# LCD.net
KiCad netlist of a schematic drawn in Altium Designer
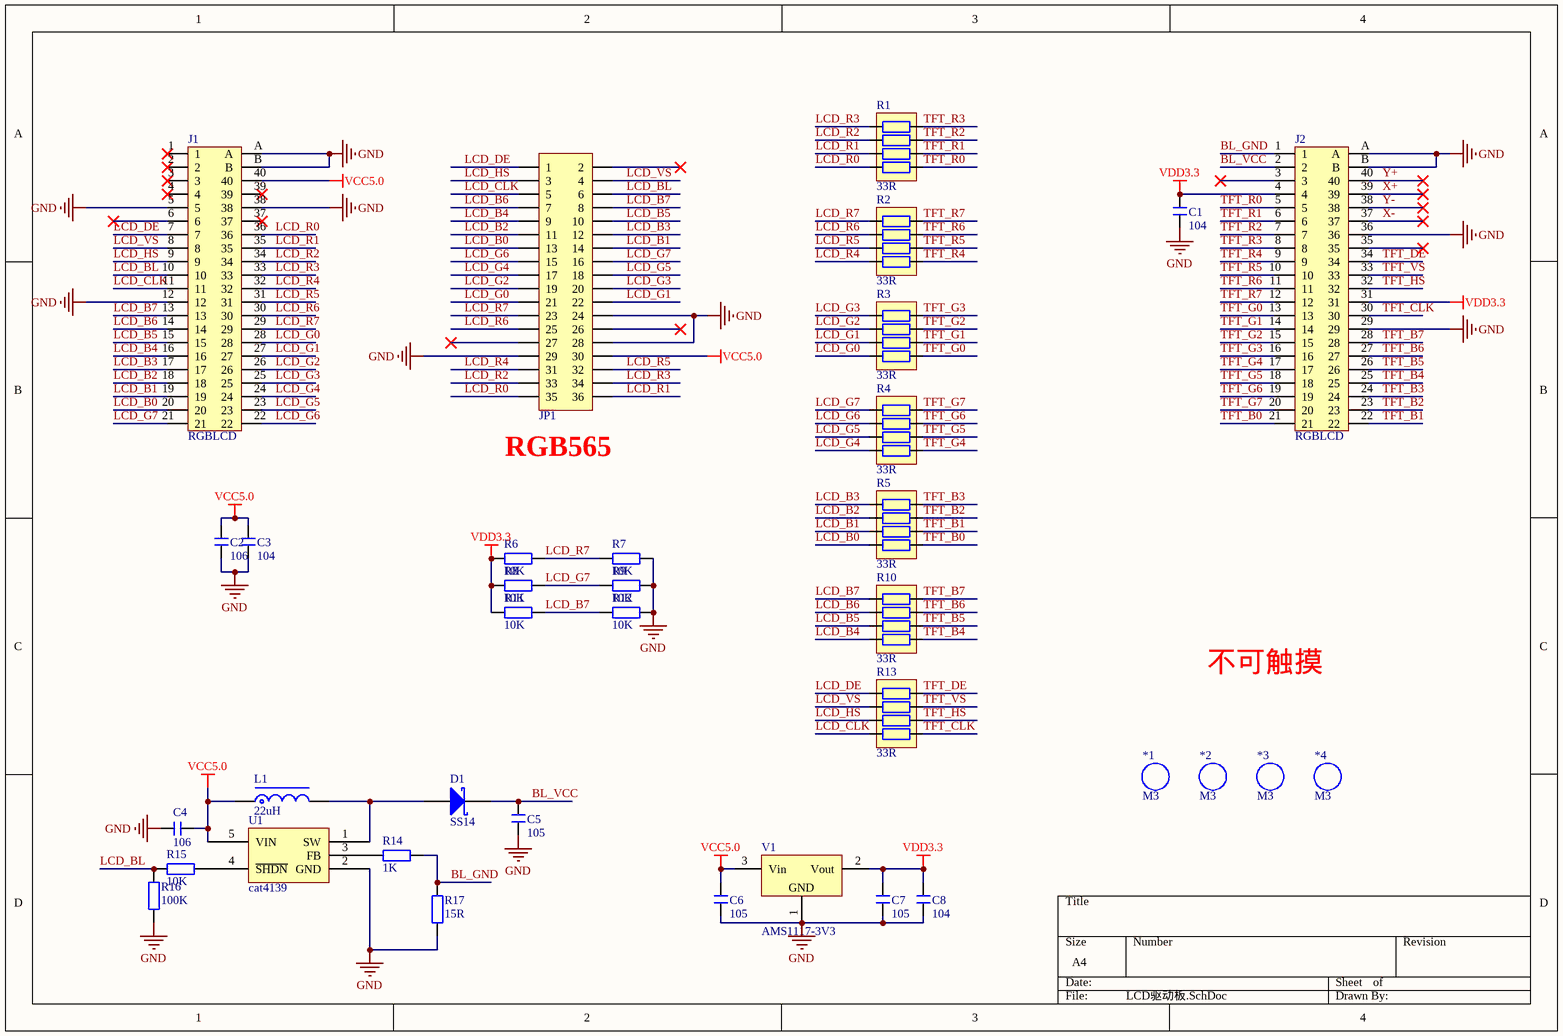
[diagram p0: LCD驱动板.SchDoc]

(export (version "E")
  (design (tool "Eeschema 10.0.6"))
  (components
    (comp (ref "*1")
      (value "M3")
      (footprint "M3 125X200")
      (description "铜柱孔")
      (fields (field (name "版权归属") "封装库来自淘宝 ID：黄晶宝石"))
      (libsource (lib "4.1 - 未分类器件") (part "M3"))
    )
    (comp (ref "*2")
      (value "M3")
      (footprint "M3 125X200")
      (description "铜柱孔")
      (fields (field (name "版权归属") "封装库来自淘宝 ID：黄晶宝石"))
      (libsource (lib "4.1 - 未分类器件") (part "M3"))
    )
    (comp (ref "*3")
      (value "M3")
      (footprint "M3 125X200")
      (description "铜柱孔")
      (fields (field (name "版权归属") "封装库来自淘宝 ID：黄晶宝石"))
      (libsource (lib "4.1 - 未分类器件") (part "M3"))
    )
    (comp (ref "*4")
      (value "M3")
      (footprint "M3 125X200")
      (description "铜柱孔")
      (fields (field (name "版权归属") "封装库来自淘宝 ID：黄晶宝石"))
      (libsource (lib "4.1 - 未分类器件") (part "M3"))
    )
    (comp (ref "C1")
      (value "104")
      (footprint "C 0603_L")
      (description "贴片电容")
      (libsource (lib "0.1 - 电阻-电容-电感") (part "C"))
    )
    (comp (ref "C2")
      (value "106")
      (footprint "C 0805_L")
      (description "贴片电容")
      (libsource (lib "0.1 - 电阻-电容-电感") (part "C"))
    )
    (comp (ref "C3")
      (value "104")
      (footprint "C 0603_L")
      (description "贴片电容")
      (libsource (lib "0.1 - 电阻-电容-电感") (part "C"))
    )
    (comp (ref "C4")
      (value "106")
      (footprint "C 0805_L")
      (description "贴片电容")
      (libsource (lib "0.1 - 电阻-电容-电感") (part "C"))
    )
    (comp (ref "C5")
      (value "105")
      (footprint "C 0805_L")
      (description "贴片电容")
      (libsource (lib "0.1 - 电阻-电容-电感") (part "C"))
    )
    (comp (ref "C6")
      (value "105")
      (footprint "C 0805_L")
      (description "贴片电容")
      (libsource (lib "0.1 - 电阻-电容-电感") (part "C"))
    )
    (comp (ref "C7")
      (value "105")
      (footprint "C 0805_L")
      (description "贴片电容")
      (libsource (lib "0.1 - 电阻-电容-电感") (part "C"))
    )
    (comp (ref "C8")
      (value "104")
      (footprint "C 0603_L")
      (description "贴片电容")
      (libsource (lib "0.1 - 电阻-电容-电感") (part "C"))
    )
    (comp (ref "D1")
      (value "SS14")
      (footprint "SMA")
      (description "肖特基二极管")
      (libsource (lib "0.2 -  二极管-整流桥") (part "SS14"))
    )
    (comp (ref "J1")
      (value "RGBLCD")
      (footprint "FPC-TOP40")
      (description "FPC-40P-0.5mm")
      (libsource (lib "PIONEER") (part "FPC-40"))
    )
    (comp (ref "J2")
      (value "RGBLCD")
      (footprint "FPC-TOP40")
      (description "FPC-40P-0.5mm")
      (libsource (lib "PIONEER") (part "FPC-40"))
    )
    (comp (ref "JP1")
      (value "Header 2X11")
      (footprint "HDR2.54-LI-2x18P")
      (description "18*2P接插件")
      (fields (field (name "版权归属") "封装库来自淘宝 ID：黄晶宝石"))
      (libsource (lib "5.3 - 接插件-脚距2.54 (100mil) ") (part "Header 18X2"))
    )
    (comp (ref "L1")
      (value "22uH")
      (footprint "NR5020")
      (description "NR磁胶电感")
      (fields (field (name "版权归属") "来自淘宝 ID：黄晶宝石"))
      (libsource (lib "0.1 - 电阻-电容-电感") (part "L-NR"))
    )
    (comp (ref "R1")
      (value "33R")
      (footprint "RCA-8P4R-0402")
      (description "贴片排阻")
      (fields (field (name "版权归属") "封装库来自淘宝 ID：黄晶宝石"))
      (libsource (lib "0.1 - 电阻-电容-电感") (part "R-8P4R"))
    )
    (comp (ref "R2")
      (value "33R")
      (footprint "RCA-8P4R-0402")
      (description "贴片排阻")
      (fields (field (name "版权归属") "封装库来自淘宝 ID：黄晶宝石"))
      (libsource (lib "0.1 - 电阻-电容-电感") (part "R-8P4R"))
    )
    (comp (ref "R3")
      (value "33R")
      (footprint "RCA-8P4R-0402")
      (description "贴片排阻")
      (fields (field (name "版权归属") "封装库来自淘宝 ID：黄晶宝石"))
      (libsource (lib "0.1 - 电阻-电容-电感") (part "R-8P4R"))
    )
    (comp (ref "R4")
      (value "33R")
      (footprint "RCA-8P4R-0402")
      (description "贴片排阻")
      (fields (field (name "版权归属") "封装库来自淘宝 ID：黄晶宝石"))
      (libsource (lib "0.1 - 电阻-电容-电感") (part "R-8P4R"))
    )
    (comp (ref "R5")
      (value "33R")
      (footprint "RCA-8P4R-0402")
      (description "贴片排阻")
      (fields (field (name "版权归属") "封装库来自淘宝 ID：黄晶宝石"))
      (libsource (lib "0.1 - 电阻-电容-电感") (part "R-8P4R"))
    )
    (comp (ref "R6")
      (value "10K")
      (footprint "R 0603_L")
      (description "贴片电阻")
      (fields (field (name "版权归属") "来自淘宝 ID：黄晶宝石"))
      (libsource (lib "0.1 - 电阻-电容-电感") (part "R"))
    )
    (comp (ref "R7")
      (value "10K")
      (footprint "R 0603_L")
      (description "贴片电阻")
      (fields (field (name "版权归属") "来自淘宝 ID：黄晶宝石"))
      (libsource (lib "0.1 - 电阻-电容-电感") (part "R"))
    )
    (comp (ref "R8")
      (value "10K")
      (footprint "R 0603_L")
      (description "贴片电阻")
      (fields (field (name "版权归属") "来自淘宝 ID：黄晶宝石"))
      (libsource (lib "0.1 - 电阻-电容-电感") (part "R"))
    )
    (comp (ref "R9")
      (value "10K")
      (footprint "R 0603_L")
      (description "贴片电阻")
      (fields (field (name "版权归属") "来自淘宝 ID：黄晶宝石"))
      (libsource (lib "0.1 - 电阻-电容-电感") (part "R"))
    )
    (comp (ref "R10")
      (value "33R")
      (footprint "RCA-8P4R-0402")
      (description "贴片排阻")
      (fields (field (name "版权归属") "封装库来自淘宝 ID：黄晶宝石"))
      (libsource (lib "0.1 - 电阻-电容-电感") (part "R-8P4R"))
    )
    (comp (ref "R11")
      (value "10K")
      (footprint "R 0603_L")
      (description "贴片电阻")
      (fields (field (name "版权归属") "来自淘宝 ID：黄晶宝石"))
      (libsource (lib "0.1 - 电阻-电容-电感") (part "R"))
    )
    (comp (ref "R12")
      (value "10K")
      (footprint "R 0603_L")
      (description "贴片电阻")
      (fields (field (name "版权归属") "来自淘宝 ID：黄晶宝石"))
      (libsource (lib "0.1 - 电阻-电容-电感") (part "R"))
    )
    (comp (ref "R13")
      (value "33R")
      (footprint "RCA-8P4R-0402")
      (description "贴片排阻")
      (fields (field (name "版权归属") "封装库来自淘宝 ID：黄晶宝石"))
      (libsource (lib "0.1 - 电阻-电容-电感") (part "R-8P4R"))
    )
    (comp (ref "R14")
      (value "1K")
      (footprint "R 0603_L")
      (description "贴片电阻")
      (fields (field (name "版权归属") "来自淘宝 ID：黄晶宝石"))
      (libsource (lib "0.1 - 电阻-电容-电感") (part "R"))
    )
    (comp (ref "R15")
      (value "10K")
      (footprint "R 0603_L")
      (description "贴片电阻")
      (fields (field (name "版权归属") "来自淘宝 ID：黄晶宝石"))
      (libsource (lib "0.1 - 电阻-电容-电感") (part "R"))
    )
    (comp (ref "R16")
      (value "100K")
      (footprint "R 0603_L")
      (description "贴片电阻")
      (fields (field (name "版权归属") "来自淘宝 ID：黄晶宝石"))
      (libsource (lib "0.1 - 电阻-电容-电感") (part "R"))
    )
    (comp (ref "R17")
      (value "15R")
      (footprint "R 0603_L")
      (description "贴片电阻")
      (fields (field (name "版权归属") "来自淘宝 ID：黄晶宝石"))
      (libsource (lib "0.1 - 电阻-电容-电感") (part "R"))
    )
    (comp (ref "U1") (value "cat4139") (footprint "SOT23-5") (libsource (lib "Schlib1") (part "cat4139")))
    (comp (ref "V1")
      (value "AMS1117-3V3")
      (footprint "SOT223_L")
      (description "三端稳压芯片")
      (libsource (lib "1.1 - 电源类芯片") (part "AMS1117"))
    )
  )
  (nets
    (net (code "1") (name "/BL_GND") (class "Default")
      (node (ref "J2") (pin "1") (pinfunction "1_1") (pintype "passive"))
      (node (ref "R14") (pin "2") (pinfunction "2_2") (pintype "passive"))
      (node (ref "R17") (pin "2") (pinfunction "2_2") (pintype "passive"))
    )
    (net (code "2") (name "/BL_VCC") (class "Default")
      (node (ref "C5") (pin "2") (pinfunction "2_2") (pintype "passive"))
      (node (ref "D1") (pin "2") (pinfunction "K_2") (pintype "passive"))
      (node (ref "J2") (pin "2") (pinfunction "2_2") (pintype "passive"))
    )
    (net (code "3") (name "/LCD_B0") (class "Default")
      (node (ref "J1") (pin "20") (pinfunction "20_20") (pintype "passive"))
      (node (ref "JP1") (pin "13") (pinfunction "13_13") (pintype "passive"))
      (node (ref "R5") (pin "1") (pinfunction "1_1") (pintype "passive"))
    )
    (net (code "4") (name "/LCD_B1") (class "Default")
      (node (ref "J1") (pin "19") (pinfunction "19_19") (pintype "passive"))
      (node (ref "JP1") (pin "14") (pinfunction "14_14") (pintype "passive"))
      (node (ref "R5") (pin "2") (pinfunction "2_2") (pintype "passive"))
    )
    (net (code "5") (name "/LCD_B2") (class "Default")
      (node (ref "J1") (pin "18") (pinfunction "18_18") (pintype "passive"))
      (node (ref "JP1") (pin "11") (pinfunction "11_11") (pintype "passive"))
      (node (ref "R5") (pin "3") (pinfunction "3_3") (pintype "passive"))
    )
    (net (code "6") (name "/LCD_B3") (class "Default")
      (node (ref "J1") (pin "17") (pinfunction "17_17") (pintype "passive"))
      (node (ref "JP1") (pin "12") (pinfunction "12_12") (pintype "passive"))
      (node (ref "R5") (pin "4") (pinfunction "4_4") (pintype "passive"))
    )
    (net (code "7") (name "/LCD_B4") (class "Default")
      (node (ref "J1") (pin "16") (pinfunction "16_16") (pintype "passive"))
      (node (ref "JP1") (pin "9") (pinfunction "9_9") (pintype "passive"))
      (node (ref "R10") (pin "1") (pinfunction "1_1") (pintype "passive"))
    )
    (net (code "8") (name "/LCD_B5") (class "Default")
      (node (ref "J1") (pin "15") (pinfunction "15_15") (pintype "passive"))
      (node (ref "JP1") (pin "10") (pinfunction "10_10") (pintype "passive"))
      (node (ref "R10") (pin "2") (pinfunction "2_2") (pintype "passive"))
    )
    (net (code "9") (name "/LCD_B6") (class "Default")
      (node (ref "J1") (pin "14") (pinfunction "14_14") (pintype "passive"))
      (node (ref "JP1") (pin "7") (pinfunction "7_7") (pintype "passive"))
      (node (ref "R10") (pin "3") (pinfunction "3_3") (pintype "passive"))
    )
    (net (code "10") (name "/LCD_B7") (class "Default")
      (node (ref "J1") (pin "13") (pinfunction "13_13") (pintype "passive"))
      (node (ref "JP1") (pin "8") (pinfunction "8_8") (pintype "passive"))
      (node (ref "R10") (pin "4") (pinfunction "4_4") (pintype "passive"))
      (node (ref "R11") (pin "2") (pinfunction "2_2") (pintype "passive"))
      (node (ref "R12") (pin "1") (pinfunction "1_1") (pintype "passive"))
    )
    (net (code "11") (name "/LCD_BL") (class "Default")
      (node (ref "J1") (pin "10") (pinfunction "10_10") (pintype "passive"))
      (node (ref "JP1") (pin "6") (pinfunction "6_6") (pintype "passive"))
      (node (ref "R15") (pin "1") (pinfunction "1_1") (pintype "passive"))
      (node (ref "R16") (pin "2") (pinfunction "2_2") (pintype "passive"))
    )
    (net (code "12") (name "/LCD_CLK") (class "Default")
      (node (ref "J1") (pin "11") (pinfunction "11_11") (pintype "passive"))
      (node (ref "JP1") (pin "5") (pinfunction "5_5") (pintype "passive"))
      (node (ref "R13") (pin "1") (pinfunction "1_1") (pintype "passive"))
    )
    (net (code "13") (name "/LCD_DE") (class "Default")
      (node (ref "J1") (pin "7") (pinfunction "7_7") (pintype "passive"))
      (node (ref "JP1") (pin "1") (pinfunction "1_1") (pintype "passive"))
      (node (ref "R13") (pin "4") (pinfunction "4_4") (pintype "passive"))
    )
    (net (code "14") (name "/LCD_G0") (class "Default")
      (node (ref "J1") (pin "28") (pinfunction "28_28") (pintype "passive"))
      (node (ref "JP1") (pin "21") (pinfunction "21_21") (pintype "passive"))
      (node (ref "R3") (pin "1") (pinfunction "1_1") (pintype "passive"))
    )
    (net (code "15") (name "/LCD_G1") (class "Default")
      (node (ref "J1") (pin "27") (pinfunction "27_27") (pintype "passive"))
      (node (ref "JP1") (pin "22") (pinfunction "22_22") (pintype "passive"))
      (node (ref "R3") (pin "2") (pinfunction "2_2") (pintype "passive"))
    )
    (net (code "16") (name "/LCD_G2") (class "Default")
      (node (ref "J1") (pin "26") (pinfunction "26_26") (pintype "passive"))
      (node (ref "JP1") (pin "19") (pinfunction "19_19") (pintype "passive"))
      (node (ref "R3") (pin "3") (pinfunction "3_3") (pintype "passive"))
    )
    (net (code "17") (name "/LCD_G3") (class "Default")
      (node (ref "J1") (pin "25") (pinfunction "25_25") (pintype "passive"))
      (node (ref "JP1") (pin "20") (pinfunction "20_20") (pintype "passive"))
      (node (ref "R3") (pin "4") (pinfunction "4_4") (pintype "passive"))
    )
    (net (code "18") (name "/LCD_G4") (class "Default")
      (node (ref "J1") (pin "24") (pinfunction "24_24") (pintype "passive"))
      (node (ref "JP1") (pin "17") (pinfunction "17_17") (pintype "passive"))
      (node (ref "R4") (pin "1") (pinfunction "1_1") (pintype "passive"))
    )
    (net (code "19") (name "/LCD_G5") (class "Default")
      (node (ref "J1") (pin "23") (pinfunction "23_23") (pintype "passive"))
      (node (ref "JP1") (pin "18") (pinfunction "18_18") (pintype "passive"))
      (node (ref "R4") (pin "2") (pinfunction "2_2") (pintype "passive"))
    )
    (net (code "20") (name "/LCD_G6") (class "Default")
      (node (ref "J1") (pin "22") (pinfunction "22_22") (pintype "passive"))
      (node (ref "JP1") (pin "15") (pinfunction "15_15") (pintype "passive"))
      (node (ref "R4") (pin "3") (pinfunction "3_3") (pintype "passive"))
    )
    (net (code "21") (name "/LCD_G7") (class "Default")
      (node (ref "J1") (pin "21") (pinfunction "21_21") (pintype "passive"))
      (node (ref "JP1") (pin "16") (pinfunction "16_16") (pintype "passive"))
      (node (ref "R4") (pin "4") (pinfunction "4_4") (pintype "passive"))
      (node (ref "R8") (pin "2") (pinfunction "2_2") (pintype "passive"))
      (node (ref "R9") (pin "1") (pinfunction "1_1") (pintype "passive"))
    )
    (net (code "22") (name "/LCD_HS") (class "Default")
      (node (ref "J1") (pin "9") (pinfunction "9_9") (pintype "passive"))
      (node (ref "JP1") (pin "3") (pinfunction "3_3") (pintype "passive"))
      (node (ref "R13") (pin "2") (pinfunction "2_2") (pintype "passive"))
    )
    (net (code "23") (name "/LCD_R0") (class "Default")
      (node (ref "J1") (pin "36") (pinfunction "36_36") (pintype "passive"))
      (node (ref "JP1") (pin "35") (pinfunction "35_35") (pintype "passive"))
      (node (ref "R1") (pin "1") (pinfunction "1_1") (pintype "passive"))
    )
    (net (code "24") (name "/LCD_R1") (class "Default")
      (node (ref "J1") (pin "35") (pinfunction "35_35") (pintype "passive"))
      (node (ref "JP1") (pin "36") (pinfunction "36_36") (pintype "passive"))
      (node (ref "R1") (pin "2") (pinfunction "2_2") (pintype "passive"))
    )
    (net (code "25") (name "/LCD_R2") (class "Default")
      (node (ref "J1") (pin "34") (pinfunction "34_34") (pintype "passive"))
      (node (ref "JP1") (pin "33") (pinfunction "33_33") (pintype "passive"))
      (node (ref "R1") (pin "3") (pinfunction "3_3") (pintype "passive"))
    )
    (net (code "26") (name "/LCD_R3") (class "Default")
      (node (ref "J1") (pin "33") (pinfunction "33_33") (pintype "passive"))
      (node (ref "JP1") (pin "34") (pinfunction "34_34") (pintype "passive"))
      (node (ref "R1") (pin "4") (pinfunction "4_4") (pintype "passive"))
    )
    (net (code "27") (name "/LCD_R4") (class "Default")
      (node (ref "J1") (pin "32") (pinfunction "32_32") (pintype "passive"))
      (node (ref "JP1") (pin "31") (pinfunction "31_31") (pintype "passive"))
      (node (ref "R2") (pin "1") (pinfunction "1_1") (pintype "passive"))
    )
    (net (code "28") (name "/LCD_R5") (class "Default")
      (node (ref "J1") (pin "31") (pinfunction "31_31") (pintype "passive"))
      (node (ref "JP1") (pin "32") (pinfunction "32_32") (pintype "passive"))
      (node (ref "R2") (pin "2") (pinfunction "2_2") (pintype "passive"))
    )
    (net (code "29") (name "/LCD_R6") (class "Default")
      (node (ref "J1") (pin "30") (pinfunction "30_30") (pintype "passive"))
      (node (ref "JP1") (pin "25") (pinfunction "25_25") (pintype "passive"))
      (node (ref "R2") (pin "3") (pinfunction "3_3") (pintype "passive"))
    )
    (net (code "30") (name "/LCD_R7") (class "Default")
      (node (ref "J1") (pin "29") (pinfunction "29_29") (pintype "passive"))
      (node (ref "JP1") (pin "23") (pinfunction "23_23") (pintype "passive"))
      (node (ref "R2") (pin "4") (pinfunction "4_4") (pintype "passive"))
      (node (ref "R6") (pin "2") (pinfunction "2_2") (pintype "passive"))
      (node (ref "R7") (pin "1") (pinfunction "1_1") (pintype "passive"))
    )
    (net (code "31") (name "/LCD_VS") (class "Default")
      (node (ref "J1") (pin "8") (pinfunction "8_8") (pintype "passive"))
      (node (ref "JP1") (pin "4") (pinfunction "4_4") (pintype "passive"))
      (node (ref "R13") (pin "3") (pinfunction "3_3") (pintype "passive"))
    )
    (net (code "32") (name "/TFT_B0") (class "Default")
      (node (ref "J2") (pin "21") (pinfunction "21_21") (pintype "passive"))
      (node (ref "R5") (pin "8") (pinfunction "8_8") (pintype "passive"))
    )
    (net (code "33") (name "/TFT_B1") (class "Default")
      (node (ref "J2") (pin "22") (pinfunction "22_22") (pintype "passive"))
      (node (ref "R5") (pin "7") (pinfunction "7_7") (pintype "passive"))
    )
    (net (code "34") (name "/TFT_B2") (class "Default")
      (node (ref "J2") (pin "23") (pinfunction "23_23") (pintype "passive"))
      (node (ref "R5") (pin "6") (pinfunction "6_6") (pintype "passive"))
    )
    (net (code "35") (name "/TFT_B3") (class "Default")
      (node (ref "J2") (pin "24") (pinfunction "24_24") (pintype "passive"))
      (node (ref "R5") (pin "5") (pinfunction "5_5") (pintype "passive"))
    )
    (net (code "36") (name "/TFT_B4") (class "Default")
      (node (ref "J2") (pin "25") (pinfunction "25_25") (pintype "passive"))
      (node (ref "R10") (pin "8") (pinfunction "8_8") (pintype "passive"))
    )
    (net (code "37") (name "/TFT_B5") (class "Default")
      (node (ref "J2") (pin "26") (pinfunction "26_26") (pintype "passive"))
      (node (ref "R10") (pin "7") (pinfunction "7_7") (pintype "passive"))
    )
    (net (code "38") (name "/TFT_B6") (class "Default")
      (node (ref "J2") (pin "27") (pinfunction "27_27") (pintype "passive"))
      (node (ref "R10") (pin "6") (pinfunction "6_6") (pintype "passive"))
    )
    (net (code "39") (name "/TFT_B7") (class "Default")
      (node (ref "J2") (pin "28") (pinfunction "28_28") (pintype "passive"))
      (node (ref "R10") (pin "5") (pinfunction "5_5") (pintype "passive"))
    )
    (net (code "40") (name "/TFT_CLK") (class "Default")
      (node (ref "J2") (pin "30") (pinfunction "30_30") (pintype "passive"))
      (node (ref "R13") (pin "8") (pinfunction "8_8") (pintype "passive"))
    )
    (net (code "41") (name "/TFT_DE") (class "Default")
      (node (ref "J2") (pin "34") (pinfunction "34_34") (pintype "passive"))
      (node (ref "R13") (pin "5") (pinfunction "5_5") (pintype "passive"))
    )
    (net (code "42") (name "/TFT_G0") (class "Default")
      (node (ref "J2") (pin "13") (pinfunction "13_13") (pintype "passive"))
      (node (ref "R3") (pin "8") (pinfunction "8_8") (pintype "passive"))
    )
    (net (code "43") (name "/TFT_G1") (class "Default")
      (node (ref "J2") (pin "14") (pinfunction "14_14") (pintype "passive"))
      (node (ref "R3") (pin "7") (pinfunction "7_7") (pintype "passive"))
    )
    (net (code "44") (name "/TFT_G2") (class "Default")
      (node (ref "J2") (pin "15") (pinfunction "15_15") (pintype "passive"))
      (node (ref "R3") (pin "6") (pinfunction "6_6") (pintype "passive"))
    )
    (net (code "45") (name "/TFT_G3") (class "Default")
      (node (ref "J2") (pin "16") (pinfunction "16_16") (pintype "passive"))
      (node (ref "R3") (pin "5") (pinfunction "5_5") (pintype "passive"))
    )
    (net (code "46") (name "/TFT_G4") (class "Default")
      (node (ref "J2") (pin "17") (pinfunction "17_17") (pintype "passive"))
      (node (ref "R4") (pin "8") (pinfunction "8_8") (pintype "passive"))
    )
    (net (code "47") (name "/TFT_G5") (class "Default")
      (node (ref "J2") (pin "18") (pinfunction "18_18") (pintype "passive"))
      (node (ref "R4") (pin "7") (pinfunction "7_7") (pintype "passive"))
    )
    (net (code "48") (name "/TFT_G6") (class "Default")
      (node (ref "J2") (pin "19") (pinfunction "19_19") (pintype "passive"))
      (node (ref "R4") (pin "6") (pinfunction "6_6") (pintype "passive"))
    )
    (net (code "49") (name "/TFT_G7") (class "Default")
      (node (ref "J2") (pin "20") (pinfunction "20_20") (pintype "passive"))
      (node (ref "R4") (pin "5") (pinfunction "5_5") (pintype "passive"))
    )
    (net (code "50") (name "/TFT_HS") (class "Default")
      (node (ref "J2") (pin "32") (pinfunction "32_32") (pintype "passive"))
      (node (ref "R13") (pin "7") (pinfunction "7_7") (pintype "passive"))
    )
    (net (code "51") (name "/TFT_R0") (class "Default")
      (node (ref "J2") (pin "5") (pinfunction "5_5") (pintype "passive"))
      (node (ref "R1") (pin "8") (pinfunction "8_8") (pintype "passive"))
    )
    (net (code "52") (name "/TFT_R1") (class "Default")
      (node (ref "J2") (pin "6") (pinfunction "6_6") (pintype "passive"))
      (node (ref "R1") (pin "7") (pinfunction "7_7") (pintype "passive"))
    )
    (net (code "53") (name "/TFT_R2") (class "Default")
      (node (ref "J2") (pin "7") (pinfunction "7_7") (pintype "passive"))
      (node (ref "R1") (pin "6") (pinfunction "6_6") (pintype "passive"))
    )
    (net (code "54") (name "/TFT_R3") (class "Default")
      (node (ref "J2") (pin "8") (pinfunction "8_8") (pintype "passive"))
      (node (ref "R1") (pin "5") (pinfunction "5_5") (pintype "passive"))
    )
    (net (code "55") (name "/TFT_R4") (class "Default")
      (node (ref "J2") (pin "9") (pinfunction "9_9") (pintype "passive"))
      (node (ref "R2") (pin "8") (pinfunction "8_8") (pintype "passive"))
    )
    (net (code "56") (name "/TFT_R5") (class "Default")
      (node (ref "J2") (pin "10") (pinfunction "10_10") (pintype "passive"))
      (node (ref "R2") (pin "7") (pinfunction "7_7") (pintype "passive"))
    )
    (net (code "57") (name "/TFT_R6") (class "Default")
      (node (ref "J2") (pin "11") (pinfunction "11_11") (pintype "passive"))
      (node (ref "R2") (pin "6") (pinfunction "6_6") (pintype "passive"))
    )
    (net (code "58") (name "/TFT_R7") (class "Default")
      (node (ref "J2") (pin "12") (pinfunction "12_12") (pintype "passive"))
      (node (ref "R2") (pin "5") (pinfunction "5_5") (pintype "passive"))
    )
    (net (code "59") (name "/TFT_VS") (class "Default")
      (node (ref "J2") (pin "33") (pinfunction "33_33") (pintype "passive"))
      (node (ref "R13") (pin "6") (pinfunction "6_6") (pintype "passive"))
    )
    (net (code "60") (name "/X+") (class "Default")
      (node (ref "J2") (pin "39") (pinfunction "39_39") (pintype "passive+no_connect"))
    )
    (net (code "61") (name "/X-") (class "Default")
      (node (ref "J2") (pin "37") (pinfunction "37_37") (pintype "passive+no_connect"))
    )
    (net (code "62") (name "/Y+") (class "Default")
      (node (ref "J2") (pin "40") (pinfunction "40_40") (pintype "passive+no_connect"))
    )
    (net (code "63") (name "/Y-") (class "Default")
      (node (ref "J2") (pin "38") (pinfunction "38_38") (pintype "passive+no_connect"))
    )
    (net (code "64") (name "GND") (class "Default")
      (node (ref "C1") (pin "1") (pinfunction "1_1") (pintype "passive"))
      (node (ref "C2") (pin "2") (pinfunction "2_2") (pintype "passive"))
      (node (ref "C3") (pin "1") (pinfunction "1_1") (pintype "passive"))
      (node (ref "C4") (pin "1") (pinfunction "1_1") (pintype "passive"))
      (node (ref "C5") (pin "1") (pinfunction "1_1") (pintype "passive"))
      (node (ref "C6") (pin "1") (pinfunction "1_1") (pintype "passive"))
      (node (ref "C7") (pin "1") (pinfunction "1_1") (pintype "passive"))
      (node (ref "C8") (pin "1") (pinfunction "1_1") (pintype "passive"))
      (node (ref "J1") (pin "12") (pinfunction "12_12") (pintype "passive"))
      (node (ref "J1") (pin "38") (pinfunction "38_38") (pintype "passive"))
      (node (ref "J1") (pin "5") (pinfunction "5_5") (pintype "passive"))
      (node (ref "J1") (pin "A") (pinfunction "A_A") (pintype "passive"))
      (node (ref "J1") (pin "B") (pinfunction "B_B") (pintype "passive"))
      (node (ref "J2") (pin "29") (pinfunction "29_29") (pintype "passive"))
      (node (ref "J2") (pin "36") (pinfunction "36_36") (pintype "passive"))
      (node (ref "J2") (pin "A") (pinfunction "A_A") (pintype "passive"))
      (node (ref "J2") (pin "B") (pinfunction "B_B") (pintype "passive"))
      (node (ref "JP1") (pin "24") (pinfunction "24_24") (pintype "passive"))
      (node (ref "JP1") (pin "28") (pinfunction "28_28") (pintype "passive"))
      (node (ref "JP1") (pin "29") (pinfunction "29_29") (pintype "passive"))
      (node (ref "R12") (pin "2") (pinfunction "2_2") (pintype "passive"))
      (node (ref "R16") (pin "1") (pinfunction "1_1") (pintype "passive"))
      (node (ref "R17") (pin "1") (pinfunction "1_1") (pintype "passive"))
      (node (ref "R7") (pin "2") (pinfunction "2_2") (pintype "passive"))
      (node (ref "R9") (pin "2") (pinfunction "2_2") (pintype "passive"))
      (node (ref "U1") (pin "2") (pinfunction "GND_2") (pintype "passive"))
      (node (ref "V1") (pin "1") (pinfunction "GND_1") (pintype "passive"))
    )
    (net (code "65") (name "Net-(D1-A)") (class "Default")
      (node (ref "D1") (pin "1") (pinfunction "A_1") (pintype "passive"))
      (node (ref "L1") (pin "2") (pinfunction "2_2") (pintype "passive"))
      (node (ref "U1") (pin "1") (pinfunction "SW_1") (pintype "passive"))
    )
    (net (code "66") (name "Net-(U1-FB)") (class "Default")
      (node (ref "R14") (pin "1") (pinfunction "1_1") (pintype "passive"))
      (node (ref "U1") (pin "3") (pinfunction "FB_3") (pintype "passive"))
    )
    (net (code "67") (name "Net-(U1-~{SHDN})") (class "Default")
      (node (ref "R15") (pin "2") (pinfunction "2_2") (pintype "passive"))
      (node (ref "U1") (pin "4") (pinfunction "~{SHDN}_4") (pintype "passive"))
    )
    (net (code "68") (name "VCC5.0") (class "Default")
      (node (ref "C2") (pin "1") (pinfunction "1_1") (pintype "passive"))
      (node (ref "C3") (pin "2") (pinfunction "2_2") (pintype "passive"))
      (node (ref "C4") (pin "2") (pinfunction "2_2") (pintype "passive"))
      (node (ref "C6") (pin "2") (pinfunction "2_2") (pintype "passive"))
      (node (ref "J1") (pin "40") (pinfunction "40_40") (pintype "passive"))
      (node (ref "JP1") (pin "30") (pinfunction "30_30") (pintype "passive"))
      (node (ref "L1") (pin "1") (pinfunction "1_1") (pintype "passive"))
      (node (ref "U1") (pin "5") (pinfunction "VIN_5") (pintype "passive"))
      (node (ref "V1") (pin "3") (pinfunction "Vin_3") (pintype "passive"))
    )
    (net (code "69") (name "VDD3.3") (class "Default")
      (node (ref "C1") (pin "2") (pinfunction "2_2") (pintype "passive"))
      (node (ref "C7") (pin "2") (pinfunction "2_2") (pintype "passive"))
      (node (ref "C8") (pin "2") (pinfunction "2_2") (pintype "passive"))
      (node (ref "J2") (pin "31") (pinfunction "31_31") (pintype "passive"))
      (node (ref "J2") (pin "4") (pinfunction "4_4") (pintype "passive"))
      (node (ref "R11") (pin "1") (pinfunction "1_1") (pintype "passive"))
      (node (ref "R6") (pin "1") (pinfunction "1_1") (pintype "passive"))
      (node (ref "R8") (pin "1") (pinfunction "1_1") (pintype "passive"))
      (node (ref "V1") (pin "2") (pinfunction "Vout_2") (pintype "passive"))
    )
    (net (code "70") (name "unconnected-(J1-Pad1)") (class "Default")
      (node (ref "J1") (pin "1") (pinfunction "1_1") (pintype "passive+no_connect"))
    )
    (net (code "71") (name "unconnected-(J1-Pad2)") (class "Default")
      (node (ref "J1") (pin "2") (pinfunction "2_2") (pintype "passive+no_connect"))
    )
    (net (code "72") (name "unconnected-(J1-Pad3)") (class "Default")
      (node (ref "J1") (pin "3") (pinfunction "3_3") (pintype "passive+no_connect"))
    )
    (net (code "73") (name "unconnected-(J1-Pad4)") (class "Default")
      (node (ref "J1") (pin "4") (pinfunction "4_4") (pintype "passive+no_connect"))
    )
    (net (code "74") (name "unconnected-(J1-Pad6)") (class "Default")
      (node (ref "J1") (pin "6") (pinfunction "6_6") (pintype "passive+no_connect"))
    )
    (net (code "75") (name "unconnected-(J1-Pad37)") (class "Default")
      (node (ref "J1") (pin "37") (pinfunction "37_37") (pintype "passive+no_connect"))
    )
    (net (code "76") (name "unconnected-(J1-Pad39)") (class "Default")
      (node (ref "J1") (pin "39") (pinfunction "39_39") (pintype "passive+no_connect"))
    )
    (net (code "77") (name "unconnected-(J2-Pad3)") (class "Default")
      (node (ref "J2") (pin "3") (pinfunction "3_3") (pintype "passive+no_connect"))
    )
    (net (code "78") (name "unconnected-(J2-Pad35)") (class "Default")
      (node (ref "J2") (pin "35") (pinfunction "35_35") (pintype "passive+no_connect"))
    )
    (net (code "79") (name "unconnected-(JP1-Pad2)") (class "Default")
      (node (ref "JP1") (pin "2") (pinfunction "2_2") (pintype "passive+no_connect"))
    )
    (net (code "80") (name "unconnected-(JP1-Pad26)") (class "Default")
      (node (ref "JP1") (pin "26") (pinfunction "26_26") (pintype "passive+no_connect"))
    )
    (net (code "81") (name "unconnected-(JP1-Pad27)") (class "Default")
      (node (ref "JP1") (pin "27") (pinfunction "27_27") (pintype "passive+no_connect"))
    )
  )
)
